# one_axis_JStep.net
KiCad netlist of a schematic drawn in EAGLE
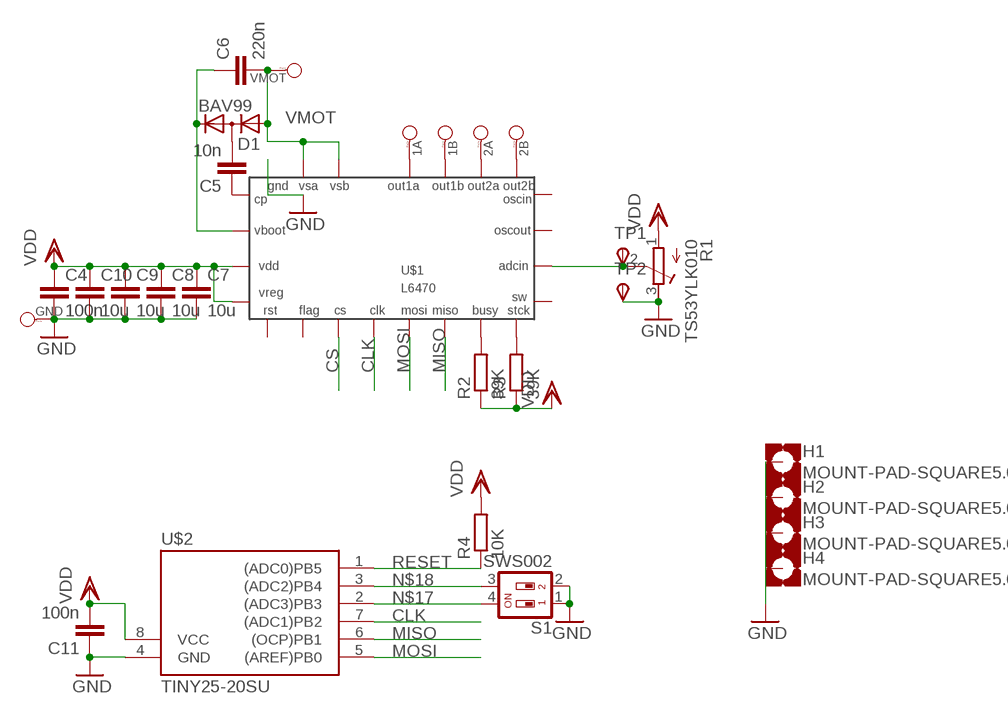
[diagram p0: schematic, sheet 1]

(export (version "E")
  (design (tool "Eeschema 10.0.6"))
  (components
    (comp (ref "1A")
      (value "WAGO256")
      (footprint "eagle-import:WAGO256")
      (libsource (lib "eagle-import") (part "WAGO256"))
    )
    (comp (ref "1B")
      (value "WAGO256")
      (footprint "eagle-import:WAGO256")
      (libsource (lib "eagle-import") (part "WAGO256"))
    )
    (comp (ref "2A")
      (value "WAGO256")
      (footprint "eagle-import:WAGO256")
      (libsource (lib "eagle-import") (part "WAGO256"))
    )
    (comp (ref "2B")
      (value "WAGO256")
      (footprint "eagle-import:WAGO256")
      (libsource (lib "eagle-import") (part "WAGO256"))
    )
    (comp (ref "C4")
      (value "100n")
      (footprint "eagle-import:C0603")
      (libsource (lib "eagle-import") (part "C-EUC0603"))
    )
    (comp (ref "C5")
      (value "10n")
      (footprint "eagle-import:C0603")
      (libsource (lib "eagle-import") (part "C-EUC0603"))
    )
    (comp (ref "C6")
      (value "220n")
      (footprint "eagle-import:C0805")
      (libsource (lib "eagle-import") (part "C-EUC0805"))
    )
    (comp (ref "C7")
      (value "10u")
      (footprint "eagle-import:C0805")
      (libsource (lib "eagle-import") (part "C-EUC0805"))
    )
    (comp (ref "C8")
      (value "10u")
      (footprint "eagle-import:C0805")
      (libsource (lib "eagle-import") (part "C-EUC0805"))
    )
    (comp (ref "C9")
      (value "10u")
      (footprint "eagle-import:C0805")
      (libsource (lib "eagle-import") (part "C-EUC0805"))
    )
    (comp (ref "C10")
      (value "10u")
      (footprint "eagle-import:C0805")
      (libsource (lib "eagle-import") (part "C-EUC0805"))
    )
    (comp (ref "C11")
      (value "100n")
      (footprint "eagle-import:C0603")
      (libsource (lib "eagle-import") (part "C-EUC0603"))
    )
    (comp (ref "D1")
      (value "BAV99")
      (footprint "eagle-import:SOT23")
      (libsource (lib "eagle-import") (part "BAV199"))
    )
    (comp (ref "GND")
      (value "WAGO256")
      (footprint "eagle-import:WAGO256")
      (libsource (lib "eagle-import") (part "WAGO256"))
    )
    (comp (ref "H1")
      (value "MOUNT-PAD-SQUARE5.0")
      (footprint "eagle-import:5,0-PAD-SQUARE")
      (libsource (lib "eagle-import") (part "MOUNT-PAD-SQUARE5.0"))
    )
    (comp (ref "H2")
      (value "MOUNT-PAD-SQUARE5.0")
      (footprint "eagle-import:5,0-PAD-SQUARE")
      (libsource (lib "eagle-import") (part "MOUNT-PAD-SQUARE5.0"))
    )
    (comp (ref "H3")
      (value "MOUNT-PAD-SQUARE5.0")
      (footprint "eagle-import:5,0-PAD-SQUARE")
      (libsource (lib "eagle-import") (part "MOUNT-PAD-SQUARE5.0"))
    )
    (comp (ref "H4")
      (value "MOUNT-PAD-SQUARE5.0")
      (footprint "eagle-import:5,0-PAD-SQUARE")
      (libsource (lib "eagle-import") (part "MOUNT-PAD-SQUARE5.0"))
    )
    (comp (ref "R1")
      (value "TS53YLK010")
      (footprint "eagle-import:RTRIM5X")
      (libsource (lib "eagle-import") (part "R-TRIMM5X"))
    )
    (comp (ref "R2")
      (value "39K")
      (footprint "eagle-import:R0603")
      (libsource (lib "eagle-import") (part "R-EU_R0603"))
    )
    (comp (ref "R3")
      (value "39K")
      (footprint "eagle-import:R0603")
      (libsource (lib "eagle-import") (part "R-EU_R0603"))
    )
    (comp (ref "R4")
      (value "10K")
      (footprint "eagle-import:R0603")
      (libsource (lib "eagle-import") (part "R-EU_R0603"))
    )
    (comp (ref "S1")
      (value "SWS002")
      (footprint "eagle-import:SMS-002")
      (libsource (lib "eagle-import") (part "SWS002"))
    )
    (comp (ref "TP1")
      (value "TPSPAD1-20")
      (footprint "eagle-import:P1-20")
      (libsource (lib "eagle-import") (part "TPSPAD1-20"))
    )
    (comp (ref "TP2")
      (value "TPSPAD1-20")
      (footprint "eagle-import:P1-20")
      (libsource (lib "eagle-import") (part "TPSPAD1-20"))
    )
    (comp (ref "U$1")
      (value "L6470")
      (footprint "eagle-import:POWERSO-36")
      (libsource (lib "eagle-import") (part "L6470"))
    )
    (comp (ref "U$2")
      (value "TINY25-20SU")
      (footprint "eagle-import:SOIC8")
      (libsource (lib "eagle-import") (part "TINY25-20SU"))
    )
    (comp (ref "VMOT")
      (value "WAGO256")
      (footprint "eagle-import:WAGO256")
      (libsource (lib "eagle-import") (part "WAGO256"))
    )
  )
  (nets
    (net (code "1") (name "/CLK") (class "Default")
      (node (ref "U$1") (pin "26") (pinfunction "CLK_26") (pintype "bidirectional"))
      (node (ref "U$2") (pin "7") (pinfunction "(ADC1)PB2_7") (pintype "bidirectional"))
    )
    (net (code "2") (name "/CS") (class "Default")
      (node (ref "U$1") (pin "30") (pinfunction "CS_30") (pintype "bidirectional"))
    )
    (net (code "3") (name "/MISO") (class "Default")
      (node (ref "U$1") (pin "25") (pinfunction "MISO_25") (pintype "bidirectional"))
      (node (ref "U$2") (pin "6") (pinfunction "(OCP)PB1_6") (pintype "bidirectional"))
    )
    (net (code "4") (name "/MOSI") (class "Default")
      (node (ref "U$1") (pin "27") (pinfunction "MOSI_27") (pintype "bidirectional"))
      (node (ref "U$2") (pin "5") (pinfunction "(AREF)PB0_5") (pintype "bidirectional"))
    )
    (net (code "5") (name "/N$17") (class "Default")
      (node (ref "S1") (pin "4") (pinfunction "4_4") (pintype "passive"))
      (node (ref "U$2") (pin "2") (pinfunction "(ADC3)PB3_2") (pintype "bidirectional"))
    )
    (net (code "6") (name "/N$18") (class "Default")
      (node (ref "S1") (pin "3") (pinfunction "3_3") (pintype "passive"))
      (node (ref "U$2") (pin "3") (pinfunction "(ADC2)PB4_3") (pintype "bidirectional"))
    )
    (net (code "7") (name "/RESET") (class "Default")
      (node (ref "R4") (pin "1") (pinfunction "1_1") (pintype "passive"))
      (node (ref "U$2") (pin "1") (pinfunction "(ADC0)PB5_1") (pintype "bidirectional"))
    )
    (net (code "8") (name "/VMOT") (class "Default")
      (node (ref "C6") (pin "2") (pinfunction "2_2") (pintype "passive"))
      (node (ref "D1") (pin "1") (pinfunction "A_1") (pintype "passive"))
      (node (ref "U$1") (pin "15") (pinfunction "VSB_15") (pintype "bidirectional"))
      (node (ref "U$1") (pin "16") (pinfunction "VSB_16") (pintype "bidirectional"))
      (node (ref "U$1") (pin "22") (pinfunction "VSB_22") (pintype "bidirectional"))
      (node (ref "U$1") (pin "23") (pinfunction "VSB_23") (pintype "bidirectional"))
      (node (ref "U$1") (pin "33") (pinfunction "VSA_33") (pintype "bidirectional"))
      (node (ref "U$1") (pin "34") (pinfunction "VSA_34") (pintype "bidirectional"))
      (node (ref "U$1") (pin "4") (pinfunction "VSA_4") (pintype "bidirectional"))
      (node (ref "U$1") (pin "5") (pinfunction "VSA_5") (pintype "bidirectional"))
      (node (ref "VMOT") (pin "1") (pinfunction "1_1") (pintype "passive"))
    )
    (net (code "9") (name "GND") (class "Default")
      (node (ref "C10") (pin "2") (pinfunction "2_2") (pintype "passive"))
      (node (ref "C11") (pin "1") (pinfunction "1_1") (pintype "passive"))
      (node (ref "C4") (pin "2") (pinfunction "2_2") (pintype "passive"))
      (node (ref "C7") (pin "2") (pinfunction "2_2") (pintype "passive"))
      (node (ref "C8") (pin "2") (pinfunction "2_2") (pintype "passive"))
      (node (ref "C9") (pin "2") (pinfunction "2_2") (pintype "passive"))
      (node (ref "GND") (pin "1") (pinfunction "1_1") (pintype "passive"))
      (node (ref "H1") (pin "B5") (pinfunction "MOUNT_B5") (pintype "passive"))
      (node (ref "H2") (pin "B5") (pinfunction "MOUNT_B5") (pintype "passive"))
      (node (ref "H3") (pin "B5") (pinfunction "MOUNT_B5") (pintype "passive"))
      (node (ref "H4") (pin "B5") (pinfunction "MOUNT_B5") (pintype "passive"))
      (node (ref "R1") (pin "3") (pinfunction "A_3") (pintype "passive"))
      (node (ref "S1") (pin "1") (pinfunction "1_1") (pintype "passive"))
      (node (ref "S1") (pin "2") (pinfunction "2_2") (pintype "passive"))
      (node (ref "TP2") (pin "TP") (pinfunction "PP_TP") (pintype "input"))
      (node (ref "U$1") (pin "1") (pinfunction "GND_1") (pintype "bidirectional"))
      (node (ref "U$1") (pin "12") (pinfunction "GND_12") (pintype "bidirectional"))
      (node (ref "U$1") (pin "19") (pinfunction "GND_19") (pintype "bidirectional"))
      (node (ref "U$1") (pin "28") (pinfunction "GND_28") (pintype "bidirectional"))
      (node (ref "U$2") (pin "4") (pinfunction "GND_4") (pintype "power_in"))
    )
    (net (code "10") (name "Net-(1A-Pad1)") (class "Default")
      (node (ref "1A") (pin "1") (pinfunction "1_1") (pintype "passive"))
      (node (ref "U$1") (pin "2") (pinfunction "O1A_2") (pintype "bidirectional"))
      (node (ref "U$1") (pin "3") (pinfunction "O1A_3") (pintype "bidirectional"))
    )
    (net (code "11") (name "Net-(1B-Pad1)") (class "Default")
      (node (ref "1B") (pin "1") (pinfunction "1_1") (pintype "passive"))
      (node (ref "U$1") (pin "17") (pinfunction "O1B_17") (pintype "bidirectional"))
      (node (ref "U$1") (pin "18") (pinfunction "O1B_18") (pintype "bidirectional"))
    )
    (net (code "12") (name "Net-(2A-Pad1)") (class "Default")
      (node (ref "2A") (pin "1") (pinfunction "1_1") (pintype "passive"))
      (node (ref "U$1") (pin "35") (pinfunction "O2A_35") (pintype "bidirectional"))
      (node (ref "U$1") (pin "36") (pinfunction "O2A_36") (pintype "bidirectional"))
    )
    (net (code "13") (name "Net-(2B-Pad1)") (class "Default")
      (node (ref "2B") (pin "1") (pinfunction "1_1") (pintype "passive"))
      (node (ref "U$1") (pin "20") (pinfunction "O2B_20") (pintype "bidirectional"))
      (node (ref "U$1") (pin "21") (pinfunction "O2B_21") (pintype "bidirectional"))
    )
    (net (code "14") (name "Net-(D1-AC)") (class "Default")
      (node (ref "C5") (pin "2") (pinfunction "2_2") (pintype "passive"))
      (node (ref "D1") (pin "3") (pinfunction "AC_3") (pintype "passive"))
    )
    (net (code "15") (name "Net-(D1-C)") (class "Default")
      (node (ref "C6") (pin "1") (pinfunction "1_1") (pintype "passive"))
      (node (ref "D1") (pin "2") (pinfunction "C_2") (pintype "passive"))
      (node (ref "U$1") (pin "14") (pinfunction "VBOOT_14") (pintype "bidirectional"))
    )
    (net (code "16") (name "Net-(R1-S)") (class "Default")
      (node (ref "R1") (pin "2") (pinfunction "S_2") (pintype "passive"))
      (node (ref "TP1") (pin "TP") (pinfunction "PP_TP") (pintype "input"))
      (node (ref "U$1") (pin "8") (pinfunction "ADCIN_8") (pintype "bidirectional"))
    )
    (net (code "17") (name "Net-(U$1-BUSY)") (class "Default")
      (node (ref "R2") (pin "2") (pinfunction "2_2") (pintype "passive"))
      (node (ref "U$1") (pin "29") (pinfunction "BUSY_29") (pintype "bidirectional"))
    )
    (net (code "18") (name "Net-(U$1-CP)") (class "Default")
      (node (ref "C5") (pin "1") (pinfunction "1_1") (pintype "passive"))
      (node (ref "U$1") (pin "13") (pinfunction "CP_13") (pintype "bidirectional"))
    )
    (net (code "19") (name "Net-(U$1-STCK)") (class "Default")
      (node (ref "R3") (pin "2") (pinfunction "2_2") (pintype "passive"))
      (node (ref "U$1") (pin "32") (pinfunction "STCK_32") (pintype "bidirectional"))
    )
    (net (code "20") (name "VDD") (class "Default")
      (node (ref "C10") (pin "1") (pinfunction "1_1") (pintype "passive"))
      (node (ref "C11") (pin "2") (pinfunction "2_2") (pintype "passive"))
      (node (ref "C4") (pin "1") (pinfunction "1_1") (pintype "passive"))
      (node (ref "C7") (pin "1") (pinfunction "1_1") (pintype "passive"))
      (node (ref "C8") (pin "1") (pinfunction "1_1") (pintype "passive"))
      (node (ref "C9") (pin "1") (pinfunction "1_1") (pintype "passive"))
      (node (ref "R1") (pin "1") (pinfunction "E_1") (pintype "passive"))
      (node (ref "R2") (pin "1") (pinfunction "1_1") (pintype "passive"))
      (node (ref "R3") (pin "1") (pinfunction "1_1") (pintype "passive"))
      (node (ref "R4") (pin "2") (pinfunction "2_2") (pintype "passive"))
      (node (ref "U$1") (pin "24") (pinfunction "VDD_24") (pintype "bidirectional"))
      (node (ref "U$1") (pin "9") (pinfunction "VREG_9") (pintype "bidirectional"))
      (node (ref "U$2") (pin "8") (pinfunction "VCC_8") (pintype "power_in"))
    )
    (net (code "21") (name "unconnected-(U$1-FLG-Pad31)") (class "Default")
      (node (ref "U$1") (pin "31") (pinfunction "FLG_31") (pintype "bidirectional"))
    )
    (net (code "22") (name "unconnected-(U$1-OSIN-Pad10)") (class "Default")
      (node (ref "U$1") (pin "10") (pinfunction "OSIN_10") (pintype "bidirectional"))
    )
    (net (code "23") (name "unconnected-(U$1-OSOUT-Pad11)") (class "Default")
      (node (ref "U$1") (pin "11") (pinfunction "OSOUT_11") (pintype "bidirectional"))
    )
    (net (code "24") (name "unconnected-(U$1-RST-Pad6)") (class "Default")
      (node (ref "U$1") (pin "6") (pinfunction "RST_6") (pintype "bidirectional"))
    )
    (net (code "25") (name "unconnected-(U$1-SW-Pad7)") (class "Default")
      (node (ref "U$1") (pin "7") (pinfunction "SW_7") (pintype "bidirectional"))
    )
  )
)
